# ArmDebuger_2-7_-HUB.net
KiCad netlist of a schematic drawn in Altium Designer
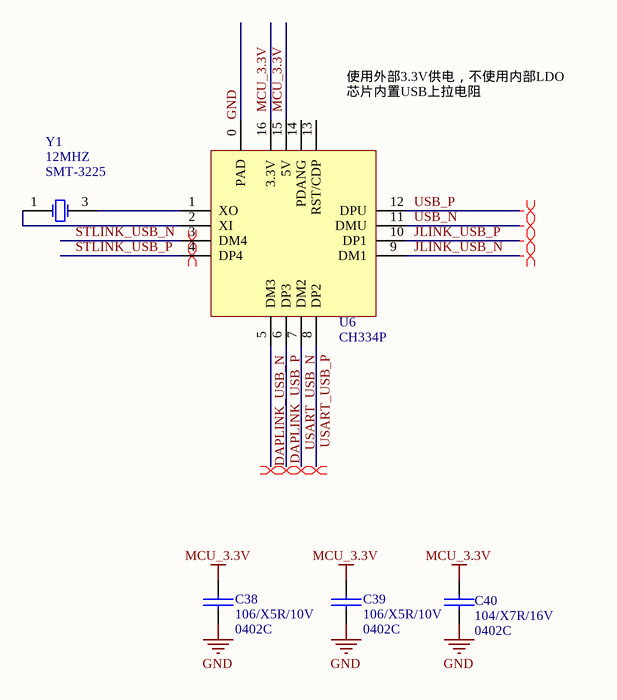
[diagram p0: ArmDebuger(2-7)-HUB.SchDoc]

(export (version "E")
  (design (tool "Eeschema 10.0.6"))
  (components
    (comp (ref "C38")
      (value "106/X5R/10V")
      (footprint "0402C-SMD-M")
      (fields (field (name "FP") "0402C"))
      (libsource (lib "*") (part "CAP"))
    )
    (comp (ref "C39")
      (value "106/X5R/10V")
      (footprint "0402C-SMD-M")
      (fields (field (name "FP") "0402C"))
      (libsource (lib "*") (part "CAP"))
    )
    (comp (ref "C40")
      (value "104/X7R/16V")
      (footprint "0402C-SMD-M")
      (fields (field (name "FP") "0402C"))
      (libsource (lib "*") (part "CAP"))
    )
    (comp (ref "U6") (value "CH334P") (footprint "QFN-16") (libsource (lib "SchLib") (part "CH334P")))
    (comp (ref "Y1")
      (value "12MHZ")
      (footprint "CRYSTAL-SMT-3225")
      (description "贴片晶振")
      (fields (field (name "FP") "SMT-3225"))
      (libsource (lib "CrystalOscillator") (part "SMD-3225_4P  25MHZ 12PF 10PPM"))
    )
  )
  (nets
    (net (code "1") (name "/DAPLINK_USB_N") (class "Default")
      (node (ref "U6") (pin "5") (pinfunction "DM3_5") (pintype "passive"))
    )
    (net (code "2") (name "/DAPLINK_USB_P") (class "Default")
      (node (ref "U6") (pin "6") (pinfunction "DP3_6") (pintype "passive"))
    )
    (net (code "3") (name "/JLINK_USB_N") (class "Default")
      (node (ref "U6") (pin "9") (pinfunction "DM1_9") (pintype "passive"))
    )
    (net (code "4") (name "/JLINK_USB_P") (class "Default")
      (node (ref "U6") (pin "10") (pinfunction "DP1_10") (pintype "passive"))
    )
    (net (code "5") (name "/STLINK_USB_N") (class "Default")
      (node (ref "U6") (pin "3") (pinfunction "DM4_3") (pintype "passive"))
    )
    (net (code "6") (name "/STLINK_USB_P") (class "Default")
      (node (ref "U6") (pin "4") (pinfunction "DP4_4") (pintype "passive"))
    )
    (net (code "7") (name "/USART_USB_N") (class "Default")
      (node (ref "U6") (pin "7") (pinfunction "DM2_7") (pintype "passive"))
    )
    (net (code "8") (name "/USART_USB_P") (class "Default")
      (node (ref "U6") (pin "8") (pinfunction "DP2_8") (pintype "passive"))
    )
    (net (code "9") (name "/USB_N") (class "Default")
      (node (ref "U6") (pin "11") (pinfunction "DMU_11") (pintype "passive"))
    )
    (net (code "10") (name "/USB_P") (class "Default")
      (node (ref "U6") (pin "12") (pinfunction "DPU_12") (pintype "passive"))
    )
    (net (code "11") (name "GND") (class "Default")
      (node (ref "C38") (pin "2") (pinfunction "1_2") (pintype "passive"))
      (node (ref "C39") (pin "2") (pinfunction "1_2") (pintype "passive"))
      (node (ref "C40") (pin "1") (pinfunction "1_1") (pintype "passive"))
      (node (ref "U6") (pin "0") (pinfunction "PAD_0") (pintype "passive"))
    )
    (net (code "12") (name "MCU_3.3V") (class "Default")
      (node (ref "C38") (pin "1") (pinfunction "1_1") (pintype "passive"))
      (node (ref "C39") (pin "1") (pinfunction "1_1") (pintype "passive"))
      (node (ref "C40") (pin "2") (pinfunction "1_2") (pintype "passive"))
      (node (ref "U6") (pin "15") (pinfunction "5V_15") (pintype "passive"))
      (node (ref "U6") (pin "16") (pinfunction "3.3V_16") (pintype "passive"))
    )
    (net (code "13") (name "Net-(U6-XI)") (class "Default")
      (node (ref "U6") (pin "2") (pinfunction "XI_2") (pintype "passive"))
      (node (ref "Y1") (pin "1") (pinfunction "OSC1_1") (pintype "passive"))
    )
    (net (code "14") (name "Net-(U6-XO)") (class "Default")
      (node (ref "U6") (pin "1") (pinfunction "XO_1") (pintype "passive"))
      (node (ref "Y1") (pin "3") (pinfunction "OSC2_3") (pintype "passive"))
    )
    (net (code "15") (name "unconnected-(U6-PDANG-Pad14)") (class "Default")
      (node (ref "U6") (pin "14") (pinfunction "PDANG_14") (pintype "passive"))
    )
    (net (code "16") (name "unconnected-(U6-RST{slash}CDP-Pad13)") (class "Default")
      (node (ref "U6") (pin "13") (pinfunction "RST/CDP_13") (pintype "passive"))
    )
  )
)
